# RelayWingTesterRevB.net
KiCad netlist of a schematic drawn in EAGLE
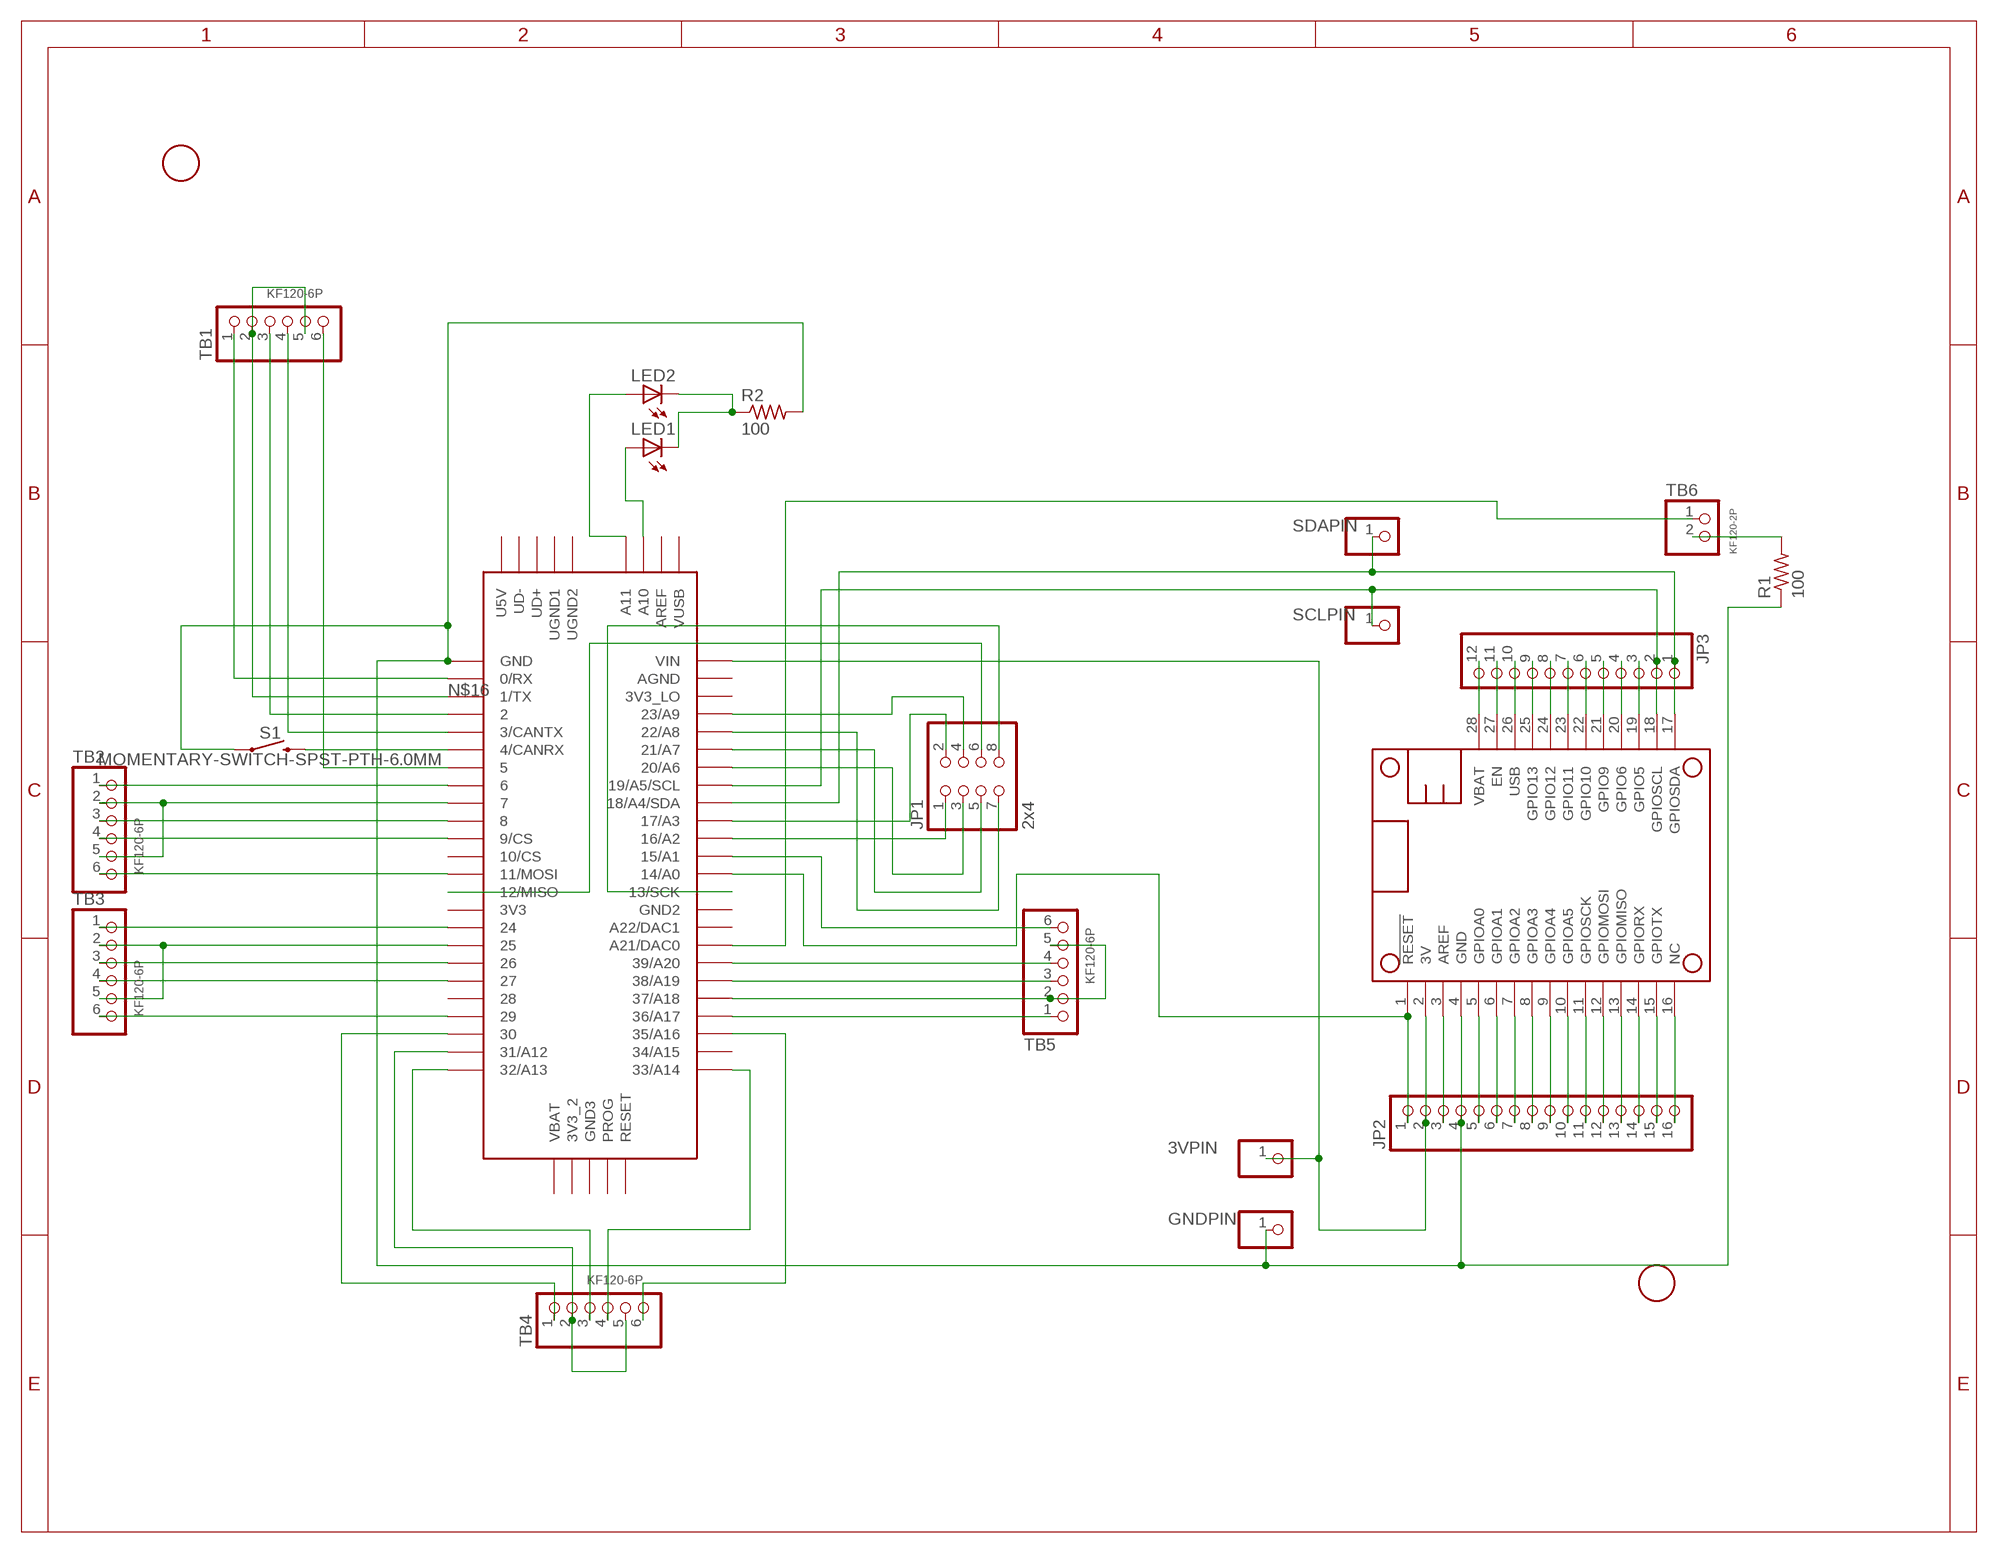
[diagram p0: schematic, sheet 1]

(export (version "E")
  (design (tool "Eeschema 10.0.6"))
  (components
    (comp (ref "3VPIN")
      (value "PINHD-1X1")
      (footprint "eagle-import:1X01")
      (libsource (lib "eagle-import") (part "PINHD-1X1"))
    )
    (comp (ref "GNDPIN")
      (value "PINHD-1X1")
      (footprint "eagle-import:1X01")
      (libsource (lib "eagle-import") (part "PINHD-1X1"))
    )
    (comp (ref "JP1")
      (value "2x4")
      (footprint "eagle-import:2X04")
      (libsource (lib "eagle-import") (part "PINHD-2X4"))
    )
    (comp (ref "JP2")
      (value "PINHD-1X16")
      (footprint "eagle-import:1X16")
      (libsource (lib "eagle-import") (part "PINHD-1X16"))
    )
    (comp (ref "JP3")
      (value "PINHD-1X12")
      (footprint "eagle-import:1X12")
      (libsource (lib "eagle-import") (part "PINHD-1X12"))
    )
    (comp (ref "LED1")
      (value "LED5MM")
      (footprint "eagle-import:LED5MM")
      (libsource (lib "eagle-import") (part "LED5MM"))
    )
    (comp (ref "LED2")
      (value "LED5MM")
      (footprint "eagle-import:LED5MM")
      (libsource (lib "eagle-import") (part "LED5MM"))
    )
    (comp (ref "MS1")
      (value "FEATHERWING_NODIM")
      (footprint "eagle-import:FEATHERWING_DIM")
      (libsource (lib "eagle-import") (part "FEATHERWING_NODIM"))
    )
    (comp (ref "R1")
      (value "100")
      (footprint "eagle-import:0207_10")
      (libsource (lib "eagle-import") (part "resistor_348_R-US_0207/10"))
    )
    (comp (ref "R2")
      (value "100")
      (footprint "eagle-import:0207_10")
      (libsource (lib "eagle-import") (part "R-US_0207/10"))
    )
    (comp (ref "S1")
      (value "MOMENTARY-SWITCH-SPST-PTH-6.0MM")
      (footprint "eagle-import:TACTILE_SWITCH_PTH_6.0MM")
      (libsource (lib "eagle-import") (part "MOMENTARY-SWITCH-SPST-PTH-6.0MM"))
    )
    (comp (ref "SCLPIN")
      (value "PINHD-1X1")
      (footprint "eagle-import:1X01")
      (libsource (lib "eagle-import") (part "PINHD-1X1"))
    )
    (comp (ref "SDAPIN")
      (value "PINHD-1X1")
      (footprint "eagle-import:1X01")
      (libsource (lib "eagle-import") (part "PINHD-1X1"))
    )
    (comp (ref "TB1")
      (value "KF120-6P")
      (footprint "eagle-import:KF120-6P_ROUND")
      (libsource (lib "eagle-import") (part "KF120-6P"))
    )
    (comp (ref "TB2")
      (value "KF120-6P")
      (footprint "eagle-import:KF120-6P_ROUND")
      (libsource (lib "eagle-import") (part "KF120-6P"))
    )
    (comp (ref "TB3")
      (value "KF120-6P")
      (footprint "eagle-import:KF120-6P_ROUND")
      (libsource (lib "eagle-import") (part "KF120-6P"))
    )
    (comp (ref "TB4")
      (value "KF120-6P")
      (footprint "eagle-import:KF120-6P_ROUND")
      (libsource (lib "eagle-import") (part "KF120-6P"))
    )
    (comp (ref "TB5")
      (value "KF120-6P")
      (footprint "eagle-import:KF120-6P_ROUND")
      (libsource (lib "eagle-import") (part "KF120-6P"))
    )
    (comp (ref "TB6")
      (value "KF120-2P")
      (footprint "eagle-import:KF120-2P_ROUND")
      (libsource (lib "eagle-import") (part "KF120-2P"))
    )
    (comp (ref "U$2")
      (value "FIDUCIAL")
      (footprint "eagle-import:FIDUCIAL_1MM")
      (libsource (lib "eagle-import") (part "FIDUCIAL"))
    )
    (comp (ref "U$3")
      (value "FIDUCIAL")
      (footprint "eagle-import:FIDUCIAL_1MM")
      (libsource (lib "eagle-import") (part "FIDUCIAL"))
    )
    (comp (ref "U$4")
      (value "TEENSY_3.5/3.6")
      (footprint "eagle-import:TEENSY_3.5_3.6")
      (libsource (lib "eagle-import") (part "TEENSY_3.5/3.6"))
    )
  )
  (nets
    (net (code "1") (name "/N$16") (class "Default")
      (node (ref "TB1") (pin "1") (pinfunction "1_1") (pintype "passive"))
      (node (ref "U$4") (pin "0/RX") (pinfunction "0/RX_0/RX") (pintype "bidirectional"))
    )
    (net (code "2") (name "Net-(JP1-Pad1)") (class "Default")
      (node (ref "JP1") (pin "1") (pinfunction "1_1") (pintype "passive"))
      (node (ref "U$4") (pin "16/A2") (pinfunction "16/A2_16/A2") (pintype "bidirectional"))
    )
    (net (code "3") (name "Net-(JP1-Pad2)") (class "Default")
      (node (ref "JP1") (pin "2") (pinfunction "2_2") (pintype "passive"))
      (node (ref "U$4") (pin "17/A3") (pinfunction "17/A3_17/A3") (pintype "bidirectional"))
    )
    (net (code "4") (name "Net-(JP1-Pad3)") (class "Default")
      (node (ref "JP1") (pin "3") (pinfunction "3_3") (pintype "passive"))
      (node (ref "U$4") (pin "20/A6") (pinfunction "20/A6_20/A6") (pintype "bidirectional"))
    )
    (net (code "5") (name "Net-(JP1-Pad4)") (class "Default")
      (node (ref "JP1") (pin "4") (pinfunction "4_4") (pintype "passive"))
      (node (ref "U$4") (pin "23/A9") (pinfunction "23/A9_23/A9") (pintype "bidirectional"))
    )
    (net (code "6") (name "Net-(JP1-Pad5)") (class "Default")
      (node (ref "JP1") (pin "5") (pinfunction "5_5") (pintype "passive"))
      (node (ref "U$4") (pin "21/A7") (pinfunction "21/A7_21/A7") (pintype "bidirectional"))
    )
    (net (code "7") (name "Net-(JP1-Pad6)") (class "Default")
      (node (ref "JP1") (pin "6") (pinfunction "6_6") (pintype "passive"))
      (node (ref "U$4") (pin "12/MISO") (pinfunction "12/MISO_12/MISO") (pintype "bidirectional"))
    )
    (net (code "8") (name "Net-(JP1-Pad7)") (class "Default")
      (node (ref "JP1") (pin "7") (pinfunction "7_7") (pintype "passive"))
      (node (ref "U$4") (pin "22/A8") (pinfunction "22/A8_22/A8") (pintype "bidirectional"))
    )
    (net (code "9") (name "Net-(JP1-Pad8)") (class "Default")
      (node (ref "JP1") (pin "8") (pinfunction "8_8") (pintype "passive"))
      (node (ref "U$4") (pin "13/SCK") (pinfunction "13/SCK_13/SCK") (pintype "bidirectional"))
    )
    (net (code "10") (name "Net-(LED1-C)") (class "Default")
      (node (ref "LED1") (pin "K") (pinfunction "C_K") (pintype "passive"))
      (node (ref "LED2") (pin "K") (pinfunction "C_K") (pintype "passive"))
      (node (ref "R2") (pin "1") (pinfunction "1_1") (pintype "passive"))
    )
    (net (code "11") (name "Net-(LED1-PadA)") (class "Default")
      (node (ref "LED1") (pin "A") (pinfunction "A_A") (pintype "passive"))
      (node (ref "U$4") (pin "A10") (pinfunction "A10_A10") (pintype "bidirectional"))
    )
    (net (code "12") (name "Net-(LED2-PadA)") (class "Default")
      (node (ref "LED2") (pin "A") (pinfunction "A_A") (pintype "passive"))
      (node (ref "U$4") (pin "A11") (pinfunction "A11_A11") (pintype "bidirectional"))
    )
    (net (code "13") (name "Net-(MS1-3V)") (class "Default")
      (node (ref "3VPIN") (pin "1") (pinfunction "1_1") (pintype "passive"))
      (node (ref "JP2") (pin "2") (pinfunction "2_2") (pintype "passive"))
      (node (ref "MS1") (pin "2") (pinfunction "3V_2") (pintype "power_in"))
      (node (ref "U$4") (pin "VIN") (pinfunction "VIN_VIN") (pintype "bidirectional"))
    )
    (net (code "14") (name "Net-(MS1-AREF)") (class "Default")
      (node (ref "JP2") (pin "3") (pinfunction "3_3") (pintype "passive"))
      (node (ref "MS1") (pin "3") (pinfunction "AREF_3") (pintype "passive"))
    )
    (net (code "15") (name "Net-(MS1-EN)") (class "Default")
      (node (ref "JP3") (pin "11") (pinfunction "11_11") (pintype "passive"))
      (node (ref "MS1") (pin "27") (pinfunction "EN_27") (pintype "passive"))
    )
    (net (code "16") (name "Net-(MS1-GND)") (class "Default")
      (node (ref "GNDPIN") (pin "1") (pinfunction "1_1") (pintype "passive"))
      (node (ref "JP2") (pin "4") (pinfunction "4_4") (pintype "passive"))
      (node (ref "MS1") (pin "4") (pinfunction "GND_4") (pintype "power_in"))
      (node (ref "R1") (pin "1") (pinfunction "1_1") (pintype "passive"))
      (node (ref "R2") (pin "2") (pinfunction "2_2") (pintype "passive"))
      (node (ref "S1") (pin "1") (pinfunction "1_1") (pintype "passive"))
      (node (ref "U$4") (pin "GND") (pinfunction "GND_GND") (pintype "bidirectional"))
    )
    (net (code "17") (name "Net-(MS1-GPIO5)") (class "Default")
      (node (ref "JP3") (pin "3") (pinfunction "3_3") (pintype "passive"))
      (node (ref "MS1") (pin "19") (pinfunction "GPIO5_19") (pintype "bidirectional"))
    )
    (net (code "18") (name "Net-(MS1-GPIO6)") (class "Default")
      (node (ref "JP3") (pin "4") (pinfunction "4_4") (pintype "passive"))
      (node (ref "MS1") (pin "20") (pinfunction "GPIO6_20") (pintype "bidirectional"))
    )
    (net (code "19") (name "Net-(MS1-GPIO9)") (class "Default")
      (node (ref "JP3") (pin "5") (pinfunction "5_5") (pintype "passive"))
      (node (ref "MS1") (pin "21") (pinfunction "GPIO9_21") (pintype "bidirectional"))
    )
    (net (code "20") (name "Net-(MS1-GPIO10)") (class "Default")
      (node (ref "JP3") (pin "6") (pinfunction "6_6") (pintype "passive"))
      (node (ref "MS1") (pin "22") (pinfunction "GPIO10_22") (pintype "bidirectional"))
    )
    (net (code "21") (name "Net-(MS1-GPIO11)") (class "Default")
      (node (ref "JP3") (pin "7") (pinfunction "7_7") (pintype "passive"))
      (node (ref "MS1") (pin "23") (pinfunction "GPIO11_23") (pintype "bidirectional"))
    )
    (net (code "22") (name "Net-(MS1-GPIO12)") (class "Default")
      (node (ref "JP3") (pin "8") (pinfunction "8_8") (pintype "passive"))
      (node (ref "MS1") (pin "24") (pinfunction "GPIO12_24") (pintype "bidirectional"))
    )
    (net (code "23") (name "Net-(MS1-GPIO13)") (class "Default")
      (node (ref "JP3") (pin "9") (pinfunction "9_9") (pintype "passive"))
      (node (ref "MS1") (pin "25") (pinfunction "GPIO13_25") (pintype "bidirectional"))
    )
    (net (code "24") (name "Net-(MS1-GPIOA0)") (class "Default")
      (node (ref "JP2") (pin "5") (pinfunction "5_5") (pintype "passive"))
      (node (ref "MS1") (pin "5") (pinfunction "GPIOA0_5") (pintype "bidirectional"))
    )
    (net (code "25") (name "Net-(MS1-GPIOA1)") (class "Default")
      (node (ref "JP2") (pin "6") (pinfunction "6_6") (pintype "passive"))
      (node (ref "MS1") (pin "6") (pinfunction "GPIOA1_6") (pintype "bidirectional"))
    )
    (net (code "26") (name "Net-(MS1-GPIOA2)") (class "Default")
      (node (ref "JP2") (pin "7") (pinfunction "7_7") (pintype "passive"))
      (node (ref "MS1") (pin "7") (pinfunction "GPIOA2_7") (pintype "bidirectional"))
    )
    (net (code "27") (name "Net-(MS1-GPIOA3)") (class "Default")
      (node (ref "JP2") (pin "8") (pinfunction "8_8") (pintype "passive"))
      (node (ref "MS1") (pin "8") (pinfunction "GPIOA3_8") (pintype "bidirectional"))
    )
    (net (code "28") (name "Net-(MS1-GPIOA4)") (class "Default")
      (node (ref "JP2") (pin "9") (pinfunction "9_9") (pintype "passive"))
      (node (ref "MS1") (pin "9") (pinfunction "GPIOA4_9") (pintype "bidirectional"))
    )
    (net (code "29") (name "Net-(MS1-GPIOA5)") (class "Default")
      (node (ref "JP2") (pin "10") (pinfunction "10_10") (pintype "passive"))
      (node (ref "MS1") (pin "10") (pinfunction "GPIOA5_10") (pintype "bidirectional"))
    )
    (net (code "30") (name "Net-(MS1-GPIOMISO)") (class "Default")
      (node (ref "JP2") (pin "13") (pinfunction "13_13") (pintype "passive"))
      (node (ref "MS1") (pin "13") (pinfunction "GPIOMISO_13") (pintype "bidirectional"))
    )
    (net (code "31") (name "Net-(MS1-GPIOMOSI)") (class "Default")
      (node (ref "JP2") (pin "12") (pinfunction "12_12") (pintype "passive"))
      (node (ref "MS1") (pin "12") (pinfunction "GPIOMOSI_12") (pintype "bidirectional"))
    )
    (net (code "32") (name "Net-(MS1-GPIORX)") (class "Default")
      (node (ref "JP2") (pin "14") (pinfunction "14_14") (pintype "passive"))
      (node (ref "MS1") (pin "14") (pinfunction "GPIORX_14") (pintype "bidirectional"))
    )
    (net (code "33") (name "Net-(MS1-GPIOSCK)") (class "Default")
      (node (ref "JP2") (pin "11") (pinfunction "11_11") (pintype "passive"))
      (node (ref "MS1") (pin "11") (pinfunction "GPIOSCK_11") (pintype "bidirectional"))
    )
    (net (code "34") (name "Net-(MS1-GPIOSCL)") (class "Default")
      (node (ref "JP3") (pin "2") (pinfunction "2_2") (pintype "passive"))
      (node (ref "MS1") (pin "18") (pinfunction "GPIOSCL_18") (pintype "bidirectional"))
      (node (ref "SCLPIN") (pin "1") (pinfunction "1_1") (pintype "passive"))
      (node (ref "U$4") (pin "19/A5/SCL") (pinfunction "19/A5/SCL_19/A5/SCL") (pintype "bidirectional"))
    )
    (net (code "35") (name "Net-(MS1-GPIOSDA)") (class "Default")
      (node (ref "JP3") (pin "1") (pinfunction "1_1") (pintype "passive"))
      (node (ref "MS1") (pin "17") (pinfunction "GPIOSDA_17") (pintype "bidirectional"))
      (node (ref "SDAPIN") (pin "1") (pinfunction "1_1") (pintype "passive"))
      (node (ref "U$4") (pin "18/A4/SDA") (pinfunction "18/A4/SDA_18/A4/SDA") (pintype "bidirectional"))
    )
    (net (code "36") (name "Net-(MS1-GPIOTX)") (class "Default")
      (node (ref "JP2") (pin "15") (pinfunction "15_15") (pintype "passive"))
      (node (ref "MS1") (pin "15") (pinfunction "GPIOTX_15") (pintype "bidirectional"))
    )
    (net (code "37") (name "Net-(MS1-NC)") (class "Default")
      (node (ref "JP2") (pin "16") (pinfunction "16_16") (pintype "passive"))
      (node (ref "MS1") (pin "16") (pinfunction "NC_16") (pintype "passive"))
    )
    (net (code "38") (name "Net-(MS1-USB)") (class "Default")
      (node (ref "JP3") (pin "10") (pinfunction "10_10") (pintype "passive"))
      (node (ref "MS1") (pin "26") (pinfunction "USB_26") (pintype "power_in"))
    )
    (net (code "39") (name "Net-(MS1-VBAT)") (class "Default")
      (node (ref "JP3") (pin "12") (pinfunction "12_12") (pintype "passive"))
      (node (ref "MS1") (pin "28") (pinfunction "VBAT_28") (pintype "power_in"))
    )
    (net (code "40") (name "Net-(MS1-~{RESET})") (class "Default")
      (node (ref "JP2") (pin "1") (pinfunction "1_1") (pintype "passive"))
      (node (ref "MS1") (pin "1") (pinfunction "~{RESET}_1") (pintype "input"))
      (node (ref "U$4") (pin "14/A0") (pinfunction "14/A0_14/A0") (pintype "bidirectional"))
    )
    (net (code "41") (name "Net-(R1-Pad2)") (class "Default")
      (node (ref "R1") (pin "2") (pinfunction "2_2") (pintype "passive"))
      (node (ref "TB6") (pin "2") (pinfunction "2_2") (pintype "passive"))
    )
    (net (code "42") (name "Net-(S1-2)") (class "Default")
      (node (ref "S1") (pin "3") (pinfunction "2_3") (pintype "passive"))
      (node (ref "U$4") (pin "4/CANRX") (pinfunction "4/CANRX_4/CANRX") (pintype "bidirectional"))
    )
    (net (code "43") (name "Net-(TB1-Pad2)") (class "Default")
      (node (ref "TB1") (pin "2") (pinfunction "2_2") (pintype "passive"))
      (node (ref "TB1") (pin "5") (pinfunction "5_5") (pintype "passive"))
      (node (ref "U$4") (pin "1/TX") (pinfunction "1/TX_1/TX") (pintype "bidirectional"))
    )
    (net (code "44") (name "Net-(TB1-Pad3)") (class "Default")
      (node (ref "TB1") (pin "3") (pinfunction "3_3") (pintype "passive"))
      (node (ref "U$4") (pin "2") (pinfunction "2_2") (pintype "bidirectional"))
    )
    (net (code "45") (name "Net-(TB1-Pad4)") (class "Default")
      (node (ref "TB1") (pin "4") (pinfunction "4_4") (pintype "passive"))
      (node (ref "U$4") (pin "3/CANTX") (pinfunction "3/CANTX_3/CANTX") (pintype "bidirectional"))
    )
    (net (code "46") (name "Net-(TB1-Pad6)") (class "Default")
      (node (ref "TB1") (pin "6") (pinfunction "6_6") (pintype "passive"))
      (node (ref "U$4") (pin "5") (pinfunction "5_5") (pintype "bidirectional"))
    )
    (net (code "47") (name "Net-(TB2-Pad1)") (class "Default")
      (node (ref "TB2") (pin "1") (pinfunction "1_1") (pintype "passive"))
      (node (ref "U$4") (pin "6") (pinfunction "6_6") (pintype "bidirectional"))
    )
    (net (code "48") (name "Net-(TB2-Pad2)") (class "Default")
      (node (ref "TB2") (pin "2") (pinfunction "2_2") (pintype "passive"))
      (node (ref "TB2") (pin "5") (pinfunction "5_5") (pintype "passive"))
      (node (ref "U$4") (pin "7") (pinfunction "7_7") (pintype "bidirectional"))
    )
    (net (code "49") (name "Net-(TB2-Pad3)") (class "Default")
      (node (ref "TB2") (pin "3") (pinfunction "3_3") (pintype "passive"))
      (node (ref "U$4") (pin "8") (pinfunction "8_8") (pintype "bidirectional"))
    )
    (net (code "50") (name "Net-(TB2-Pad4)") (class "Default")
      (node (ref "TB2") (pin "4") (pinfunction "4_4") (pintype "passive"))
      (node (ref "U$4") (pin "9/CS") (pinfunction "9/CS_9/CS") (pintype "bidirectional"))
    )
    (net (code "51") (name "Net-(TB2-Pad6)") (class "Default")
      (node (ref "TB2") (pin "6") (pinfunction "6_6") (pintype "passive"))
      (node (ref "U$4") (pin "11/MOSI") (pinfunction "11/MOSI_11/MOSI") (pintype "bidirectional"))
    )
    (net (code "52") (name "Net-(TB3-Pad1)") (class "Default")
      (node (ref "TB3") (pin "1") (pinfunction "1_1") (pintype "passive"))
      (node (ref "U$4") (pin "24") (pinfunction "24_24") (pintype "bidirectional"))
    )
    (net (code "53") (name "Net-(TB3-Pad2)") (class "Default")
      (node (ref "TB3") (pin "2") (pinfunction "2_2") (pintype "passive"))
      (node (ref "TB3") (pin "5") (pinfunction "5_5") (pintype "passive"))
      (node (ref "U$4") (pin "25") (pinfunction "25_25") (pintype "bidirectional"))
    )
    (net (code "54") (name "Net-(TB3-Pad3)") (class "Default")
      (node (ref "TB3") (pin "3") (pinfunction "3_3") (pintype "passive"))
      (node (ref "U$4") (pin "26") (pinfunction "26_26") (pintype "bidirectional"))
    )
    (net (code "55") (name "Net-(TB3-Pad4)") (class "Default")
      (node (ref "TB3") (pin "4") (pinfunction "4_4") (pintype "passive"))
      (node (ref "U$4") (pin "27") (pinfunction "27_27") (pintype "bidirectional"))
    )
    (net (code "56") (name "Net-(TB3-Pad6)") (class "Default")
      (node (ref "TB3") (pin "6") (pinfunction "6_6") (pintype "passive"))
      (node (ref "U$4") (pin "29") (pinfunction "29_29") (pintype "bidirectional"))
    )
    (net (code "57") (name "Net-(TB4-Pad1)") (class "Default")
      (node (ref "TB4") (pin "1") (pinfunction "1_1") (pintype "passive"))
      (node (ref "U$4") (pin "30") (pinfunction "30_30") (pintype "bidirectional"))
    )
    (net (code "58") (name "Net-(TB4-Pad2)") (class "Default")
      (node (ref "TB4") (pin "2") (pinfunction "2_2") (pintype "passive"))
      (node (ref "TB4") (pin "5") (pinfunction "5_5") (pintype "passive"))
      (node (ref "U$4") (pin "31/A12") (pinfunction "31/A12_31/A12") (pintype "bidirectional"))
    )
    (net (code "59") (name "Net-(TB4-Pad3)") (class "Default")
      (node (ref "TB4") (pin "3") (pinfunction "3_3") (pintype "passive"))
      (node (ref "U$4") (pin "32/A13") (pinfunction "32/A13_32/A13") (pintype "bidirectional"))
    )
    (net (code "60") (name "Net-(TB4-Pad4)") (class "Default")
      (node (ref "TB4") (pin "4") (pinfunction "4_4") (pintype "passive"))
      (node (ref "U$4") (pin "33/A14") (pinfunction "33/A14_33/A14") (pintype "bidirectional"))
    )
    (net (code "61") (name "Net-(TB4-Pad6)") (class "Default")
      (node (ref "TB4") (pin "6") (pinfunction "6_6") (pintype "passive"))
      (node (ref "U$4") (pin "35/A16") (pinfunction "35/A16_35/A16") (pintype "bidirectional"))
    )
    (net (code "62") (name "Net-(TB5-Pad1)") (class "Default")
      (node (ref "TB5") (pin "1") (pinfunction "1_1") (pintype "passive"))
      (node (ref "U$4") (pin "36/A17") (pinfunction "36/A17_36/A17") (pintype "bidirectional"))
    )
    (net (code "63") (name "Net-(TB5-Pad2)") (class "Default")
      (node (ref "TB5") (pin "2") (pinfunction "2_2") (pintype "passive"))
      (node (ref "TB5") (pin "5") (pinfunction "5_5") (pintype "passive"))
      (node (ref "U$4") (pin "37/A18") (pinfunction "37/A18_37/A18") (pintype "bidirectional"))
    )
    (net (code "64") (name "Net-(TB5-Pad3)") (class "Default")
      (node (ref "TB5") (pin "3") (pinfunction "3_3") (pintype "passive"))
      (node (ref "U$4") (pin "38/A19") (pinfunction "38/A19_38/A19") (pintype "bidirectional"))
    )
    (net (code "65") (name "Net-(TB5-Pad4)") (class "Default")
      (node (ref "TB5") (pin "4") (pinfunction "4_4") (pintype "passive"))
      (node (ref "U$4") (pin "39/A20") (pinfunction "39/A20_39/A20") (pintype "bidirectional"))
    )
    (net (code "66") (name "Net-(TB5-Pad6)") (class "Default")
      (node (ref "TB5") (pin "6") (pinfunction "6_6") (pintype "passive"))
      (node (ref "U$4") (pin "15/A1") (pinfunction "15/A1_15/A1") (pintype "bidirectional"))
    )
    (net (code "67") (name "Net-(U$4-A21{slash}DAC0)") (class "Default")
      (node (ref "TB6") (pin "1") (pinfunction "1_1") (pintype "passive"))
      (node (ref "U$4") (pin "21/DAC0") (pinfunction "A21/DAC0_21/DAC0") (pintype "bidirectional"))
    )
    (net (code "68") (name "unconnected-(U$4-Pad3V3)") (class "Default")
      (node (ref "U$4") (pin "3V3") (pinfunction "3V3_3V3") (pintype "bidirectional"))
    )
    (net (code "69") (name "unconnected-(U$4-Pad3V3_2)") (class "Default")
      (node (ref "U$4") (pin "3V3_2") (pinfunction "3V3_2_3V3_2") (pintype "bidirectional"))
    )
    (net (code "70") (name "unconnected-(U$4-Pad3V3_LO)") (class "Default")
      (node (ref "U$4") (pin "3V3_LO") (pinfunction "3V3_LO_3V3_LO") (pintype "bidirectional"))
    )
    (net (code "71") (name "unconnected-(U$4-Pad10{slash}CS)") (class "Default")
      (node (ref "U$4") (pin "10/CS") (pinfunction "10/CS_10/CS") (pintype "bidirectional"))
    )
    (net (code "72") (name "unconnected-(U$4-Pad28)") (class "Default")
      (node (ref "U$4") (pin "28") (pinfunction "28_28") (pintype "bidirectional"))
    )
    (net (code "73") (name "unconnected-(U$4-Pad34{slash}A15)") (class "Default")
      (node (ref "U$4") (pin "34/A15") (pinfunction "34/A15_34/A15") (pintype "bidirectional"))
    )
    (net (code "74") (name "unconnected-(U$4-PadA22{slash}DAC1)") (class "Default")
      (node (ref "U$4") (pin "A22/DAC1") (pinfunction "A22/DAC1_A22/DAC1") (pintype "bidirectional"))
    )
    (net (code "75") (name "unconnected-(U$4-PadAGND)") (class "Default")
      (node (ref "U$4") (pin "AGND") (pinfunction "AGND_AGND") (pintype "bidirectional"))
    )
    (net (code "76") (name "unconnected-(U$4-PadAREF)") (class "Default")
      (node (ref "U$4") (pin "AREF") (pinfunction "AREF_AREF") (pintype "bidirectional"))
    )
    (net (code "77") (name "unconnected-(U$4-PadGND2)") (class "Default")
      (node (ref "U$4") (pin "GND2") (pinfunction "GND2_GND2") (pintype "bidirectional"))
    )
    (net (code "78") (name "unconnected-(U$4-PadGND3)") (class "Default")
      (node (ref "U$4") (pin "GND3") (pinfunction "GND3_GND3") (pintype "bidirectional"))
    )
    (net (code "79") (name "unconnected-(U$4-PadPROG)") (class "Default")
      (node (ref "U$4") (pin "PROG") (pinfunction "PROG_PROG") (pintype "bidirectional"))
    )
    (net (code "80") (name "unconnected-(U$4-PadRESET)") (class "Default")
      (node (ref "U$4") (pin "RESET") (pinfunction "RESET_RESET") (pintype "bidirectional"))
    )
    (net (code "81") (name "unconnected-(U$4-PadU5V)") (class "Default")
      (node (ref "U$4") (pin "U5V") (pinfunction "U5V_U5V") (pintype "bidirectional"))
    )
    (net (code "82") (name "unconnected-(U$4-PadUD+)") (class "Default")
      (node (ref "U$4") (pin "UD+") (pinfunction "UD+_UD+") (pintype "bidirectional"))
    )
    (net (code "83") (name "unconnected-(U$4-PadUD-)") (class "Default")
      (node (ref "U$4") (pin "UD-") (pinfunction "UD-_UD-") (pintype "bidirectional"))
    )
    (net (code "84") (name "unconnected-(U$4-PadUGND1)") (class "Default")
      (node (ref "U$4") (pin "UGND1") (pinfunction "UGND1_UGND1") (pintype "bidirectional"))
    )
    (net (code "85") (name "unconnected-(U$4-PadUGND2)") (class "Default")
      (node (ref "U$4") (pin "UGND2") (pinfunction "UGND2_UGND2") (pintype "bidirectional"))
    )
    (net (code "86") (name "unconnected-(U$4-PadVBAT)") (class "Default")
      (node (ref "U$4") (pin "VBAT") (pinfunction "VBAT_VBAT") (pintype "bidirectional"))
    )
    (net (code "87") (name "unconnected-(U$4-PadVUSB)") (class "Default")
      (node (ref "U$4") (pin "VUSB") (pinfunction "VUSB_VUSB") (pintype "bidirectional"))
    )
  )
)
